# Microcontroller.net
KiCad netlist of a schematic drawn in Altium Designer
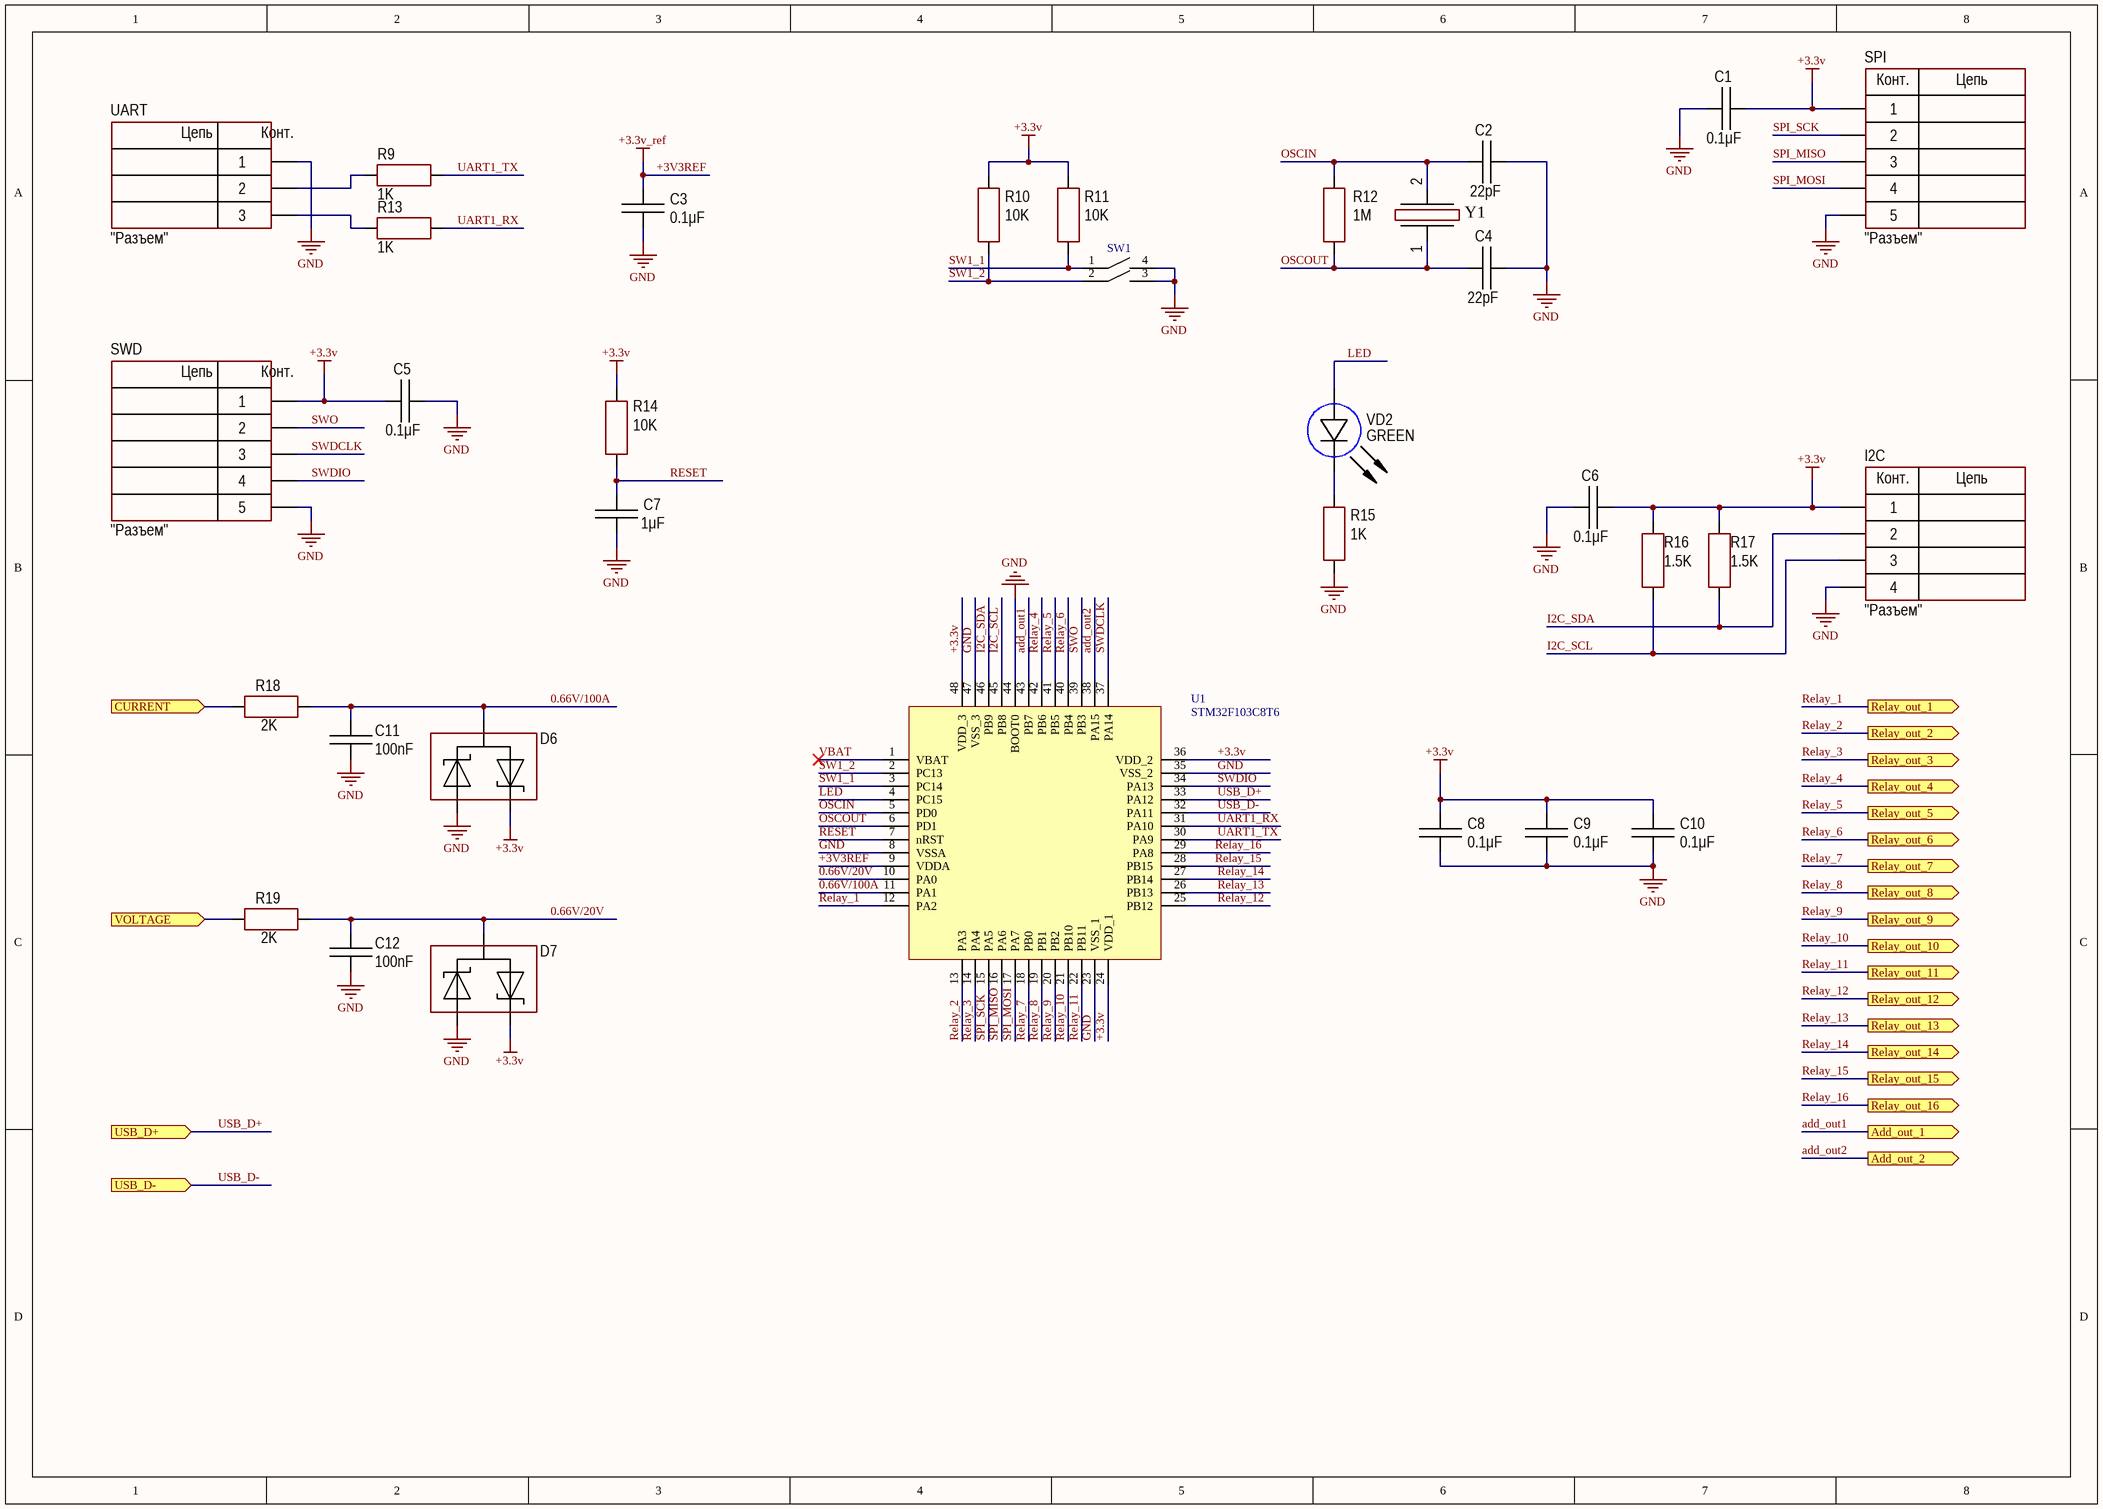
[diagram p0: Microcontroller.SchDoc]

(export (version "E")
  (design (tool "Eeschema 10.0.6"))
  (components
    (comp (ref "C1")
      (value "0.1μF")
      (footprint "StandardCase:CAP: 1206")
      (fields
        (field (name "MANUFACTURER") "Yageo")
        (field (name "PARTNUMBER") "CC1206KRX7R9BB104")
        (field (name "VALUEMANUFACTURERPARTNUMBER") "Ceramic capacitor, 0.1μF, X7R, ±10%, 50V, 1206, -55...+125°C")
      )
      (libsource (lib "Capacitor") (part "Ceramic_1206"))
    )
    (comp (ref "C2")
      (value "22pF")
      (footprint "StandardCase:CAP: 1206")
      (fields
        (field (name "MANUFACTURER") "Yageo")
        (field (name "PARTNUMBER") "CC1206KRX7R9BB104")
        (field (name "VALUEMANUFACTURERPARTNUMBER") "Ceramic capacitor, 22pF, X7R, ±10%, 50V, 1206, -55...+125°C")
      )
      (libsource (lib "Capacitor") (part "Ceramic_1206"))
    )
    (comp (ref "C3")
      (value "0.1μF")
      (footprint "StandardCase:CAP: 1206")
      (fields
        (field (name "MANUFACTURER") "Yageo")
        (field (name "PARTNUMBER") "CC1206KRX7R9BB104")
        (field (name "VALUEMANUFACTURERPARTNUMBER") "Ceramic capacitor, 0.1μF, X7R, ±10%, 50V, 1206, -55...+125°C")
      )
      (libsource (lib "Capacitor") (part "Ceramic_1206"))
    )
    (comp (ref "C4")
      (value "22pF")
      (footprint "StandardCase:CAP: 1206")
      (fields
        (field (name "MANUFACTURER") "Yageo")
        (field (name "PARTNUMBER") "CC1206KRX7R9BB104")
        (field (name "VALUEMANUFACTURERPARTNUMBER") "Ceramic capacitor, 22pF, X7R, ±10%, 50V, 1206, -55...+125°C")
      )
      (libsource (lib "Capacitor") (part "Ceramic_1206"))
    )
    (comp (ref "C5")
      (value "0.1μF")
      (footprint "StandardCase:CAP: 1206")
      (fields
        (field (name "MANUFACTURER") "Yageo")
        (field (name "PARTNUMBER") "CC1206KRX7R9BB104")
        (field (name "VALUEMANUFACTURERPARTNUMBER") "Ceramic capacitor, 0.1μF, X7R, ±10%, 50V, 1206, -55...+125°C")
      )
      (libsource (lib "Capacitor") (part "Ceramic_1206"))
    )
    (comp (ref "C6")
      (value "0.1μF")
      (footprint "StandardCase:CAP: 1206")
      (fields
        (field (name "MANUFACTURER") "Yageo")
        (field (name "PARTNUMBER") "CC1206KRX7R9BB104")
        (field (name "VALUEMANUFACTURERPARTNUMBER") "Ceramic capacitor, 0.1μF, X7R, ±10%, 50V, 1206, -55...+125°C")
      )
      (libsource (lib "Capacitor") (part "Ceramic_1206"))
    )
    (comp (ref "C7")
      (value "1μF")
      (footprint "StandardCase:CAP: 1206")
      (fields
        (field (name "MANUFACTURER") "Yageo")
        (field (name "PARTNUMBER") "CC1206KRX7R9BB104")
        (field (name "VALUEMANUFACTURERPARTNUMBER") "Ceramic capacitor, 1μF, X7R, ±10%, 50V, 1206, -55...+125°C")
      )
      (libsource (lib "Capacitor") (part "Ceramic_1206"))
    )
    (comp (ref "C8")
      (value "0.1μF")
      (footprint "StandardCase:CAP: 1206")
      (fields
        (field (name "MANUFACTURER") "Yageo")
        (field (name "PARTNUMBER") "CC1206KRX7R9BB104")
        (field (name "VALUEMANUFACTURERPARTNUMBER") "Ceramic capacitor, 0.1μF, X7R, ±10%, 50V, 1206, -55...+125°C")
      )
      (libsource (lib "Capacitor") (part "Ceramic_1206"))
    )
    (comp (ref "C9")
      (value "0.1μF")
      (footprint "StandardCase:CAP: 1206")
      (fields
        (field (name "MANUFACTURER") "Yageo")
        (field (name "PARTNUMBER") "CC1206KRX7R9BB104")
        (field (name "VALUEMANUFACTURERPARTNUMBER") "Ceramic capacitor, 0.1μF, X7R, ±10%, 50V, 1206, -55...+125°C")
      )
      (libsource (lib "Capacitor") (part "Ceramic_1206"))
    )
    (comp (ref "C10")
      (value "0.1μF")
      (footprint "StandardCase:CAP: 1206")
      (fields
        (field (name "MANUFACTURER") "Yageo")
        (field (name "PARTNUMBER") "CC1206KRX7R9BB104")
        (field (name "VALUEMANUFACTURERPARTNUMBER") "Ceramic capacitor, 0.1μF, X7R, ±10%, 50V, 1206, -55...+125°C")
      )
      (libsource (lib "Capacitor") (part "Ceramic_1206"))
    )
    (comp (ref "C11")
      (value "100nF")
      (footprint "StandardCase:CAP: 1206")
      (fields
        (field (name "MANUFACTURER") "Yageo")
        (field (name "PARTNUMBER") "CC1206KRX7R9BB104")
        (field (name "VALUEMANUFACTURERPARTNUMBER") "Ceramic capacitor, 100nF, X7R, ±10%, 50V, 1206, -55...+125°C")
      )
      (libsource (lib "Capacitor") (part "Ceramic_1206"))
    )
    (comp (ref "C12")
      (value "100nF")
      (footprint "StandardCase:CAP: 1206")
      (fields
        (field (name "MANUFACTURER") "Yageo")
        (field (name "PARTNUMBER") "CC1206KRX7R9BB104")
        (field (name "VALUEMANUFACTURERPARTNUMBER") "Ceramic capacitor, 100nF, X7R, ±10%, 50V, 1206, -55...+125°C")
      )
      (libsource (lib "Capacitor") (part "Ceramic_1206"))
    )
    (comp (ref "D6")
      (value "~")
      (footprint "StandardCase:SOT23")
      (fields
        (field (name "MANUFACTURER") "Diodes Incorporated")
        (field (name "VALUEMANUFACTURERPARTNUMBER") "BAS40-04, SOT23-3")
        (field (name "VOLTAGE") "40V")
      )
      (libsource (lib "Diode") (part "Schottky_array"))
    )
    (comp (ref "D7")
      (value "~")
      (footprint "StandardCase:SOT23")
      (fields
        (field (name "MANUFACTURER") "Diodes Incorporated")
        (field (name "VALUEMANUFACTURERPARTNUMBER") "BAS40-04, SOT23-3")
        (field (name "VOLTAGE") "40V")
      )
      (libsource (lib "Diode") (part "Schottky_array"))
    )
    (comp (ref "I2C")
      (value "~")
      (footprint "CustomCase:CON: PLS-4")
      (fields
        (field (name "MANUFACTURER") "Connfly")
        (field (name "VALUEMANUFACTURERPARTNUMBER") "Connector, 4pin, 2.54mm, 500VAC, 3A")
        (field (name "PARTNUMBER") "PLS-4")
        (field (name "COMMENTTEXT") "\"Разъем\"")
      )
      (libsource (lib "Connector") (part "PLS-4"))
    )
    (comp (ref "R9")
      (value "1K")
      (footprint "StandardCase:RES: 1206")
      (fields
        (field (name "MANUFACTURER") "Yageo")
        (field (name "PARTNUMBER") "RC1206JR-07100RL")
        (field (name "VALUEMANUFACTURERPARTNUMBER") "Resistor film, 1K, ±5%, 1206, 0.25W, -55...+125°C")
      )
      (libsource (lib "") (part "Resistor_1206_2"))
    )
    (comp (ref "R10")
      (value "10K")
      (footprint "StandardCase:RES: 1206")
      (fields
        (field (name "MANUFACTURER") "Yageo")
        (field (name "PARTNUMBER") "RC1206JR-07100RL")
        (field (name "VALUEMANUFACTURERPARTNUMBER") "Resistor, 10K, 1206")
      )
      (libsource (lib "Resistor") (part "Resistor_1206"))
    )
    (comp (ref "R11")
      (value "10K")
      (footprint "StandardCase:RES: 1206")
      (fields
        (field (name "MANUFACTURER") "Yageo")
        (field (name "PARTNUMBER") "RC1206JR-07100RL")
        (field (name "VALUEMANUFACTURERPARTNUMBER") "Resistor, 10K, 1206")
      )
      (libsource (lib "Resistor") (part "Resistor_1206"))
    )
    (comp (ref "R12")
      (value "1M")
      (footprint "StandardCase:RES: 1206")
      (fields
        (field (name "MANUFACTURER") "Yageo")
        (field (name "PARTNUMBER") "RC1206JR-07100RL")
        (field (name "VALUEMANUFACTURERPARTNUMBER") "Resistor film, 1M, ±5%, 1206, 0.25W, -55...+125°C")
      )
      (libsource (lib "Resistor") (part "Resistor_1206"))
    )
    (comp (ref "R13")
      (value "1K")
      (footprint "StandardCase:RES: 1206")
      (fields
        (field (name "MANUFACTURER") "Yageo")
        (field (name "PARTNUMBER") "RC1206JR-07100RL")
        (field (name "VALUEMANUFACTURERPARTNUMBER") "Resistor film, 1K, ±5%, 1206, 0.25W, -55...+125°C")
      )
      (libsource (lib "") (part "Resistor_1206_2"))
    )
    (comp (ref "R14")
      (value "10K")
      (footprint "StandardCase:RES: 1206")
      (fields
        (field (name "MANUFACTURER") "Yageo")
        (field (name "PARTNUMBER") "RC1206JR-07100RL")
        (field (name "VALUEMANUFACTURERPARTNUMBER") "Resistor film, 10K, ±5%, 1206, 0.25W, -55...+125°C")
      )
      (libsource (lib "Resistor") (part "Resistor_1206"))
    )
    (comp (ref "R15")
      (value "1K")
      (footprint "StandardCase:RES: 1206")
      (fields
        (field (name "MANUFACTURER") "Yageo")
        (field (name "PARTNUMBER") "RC1206JR-07100RL")
        (field (name "VALUEMANUFACTURERPARTNUMBER") "Resistor film, 1K, ±5%, 1206, 0.25W, -55...+125°C")
      )
      (libsource (lib "Resistor") (part "Resistor_1206"))
    )
    (comp (ref "R16")
      (value "1.5K")
      (footprint "StandardCase:RES: 1206")
      (fields
        (field (name "MANUFACTURER") "Yageo")
        (field (name "PARTNUMBER") "RC1206JR-07100RL")
        (field (name "VALUEMANUFACTURERPARTNUMBER") "Resistor film, 1.5K, ±5%, 1206, 0.25W, -55...+125°C")
      )
      (libsource (lib "") (part "Resistor_1206_1"))
    )
    (comp (ref "R17")
      (value "1.5K")
      (footprint "StandardCase:RES: 1206")
      (fields
        (field (name "MANUFACTURER") "Yageo")
        (field (name "PARTNUMBER") "RC1206JR-07100RL")
        (field (name "VALUEMANUFACTURERPARTNUMBER") "Resistor film, 1.5K, ±5%, 1206, 0.25W, -55...+125°C")
      )
      (libsource (lib "") (part "Resistor_1206_1"))
    )
    (comp (ref "R18")
      (value "2K")
      (footprint "StandardCase:RES: 1206")
      (fields
        (field (name "MANUFACTURER") "Yageo")
        (field (name "PARTNUMBER") "RC1206JR-07100RL")
        (field (name "VALUEMANUFACTURERPARTNUMBER") "Resistor film, 2K, ±5%, 1206, 0.25W, -55...+125°C")
      )
      (libsource (lib "") (part "Resistor_1206_2"))
    )
    (comp (ref "R19")
      (value "2K")
      (footprint "StandardCase:RES: 1206")
      (fields
        (field (name "MANUFACTURER") "Yageo")
        (field (name "PARTNUMBER") "RC1206JR-07100RL")
        (field (name "VALUEMANUFACTURERPARTNUMBER") "Resistor film, 2K, ±5%, 1206, 0.25W, -55...+125°C")
      )
      (libsource (lib "") (part "Resistor_1206_2"))
    )
    (comp (ref "SPI")
      (value "~")
      (footprint "CustomCase:CON: PLS-5")
      (fields
        (field (name "MANUFACTURER") "Connfly")
        (field (name "VALUEMANUFACTURERPARTNUMBER") "Connector, 5pin, 2.54mm, 500VAC, 3A")
        (field (name "PARTNUMBER") "PLS-5")
        (field (name "COMMENTTEXT") "\"Разъем\"")
      )
      (libsource (lib "Connector") (part "PLS-5"))
    )
    (comp (ref "SW1")
      (value "~")
      (footprint "PcbLib1:DPL-2")
      (fields
        (field (name "PARTNUMBER") "NDP-02")
        (field (name "VALUEMANUFACTURERPARTNUMBER") "NDP-02, DPL-02")
      )
      (libsource (lib "Schlib1") (part "NDP-02"))
    )
    (comp (ref "SWD")
      (value "~")
      (footprint "CustomCase:CON: PLS-5")
      (fields
        (field (name "MANUFACTURER") "Connfly")
        (field (name "VALUEMANUFACTURERPARTNUMBER") "Connector, 5pin, 2.54mm, 500VAC, 3A")
        (field (name "PARTNUMBER") "PLS-5")
        (field (name "COMMENTTEXT") "\"Разъем\"")
      )
      (libsource (lib "") (part "PLS-5_1"))
    )
    (comp (ref "U1")
      (value "STM32F103C8T6")
      (footprint "StandardCase:48-LQFP")
      (libsource (lib "Schlib1") (part "STM32F103C8T6"))
    )
    (comp (ref "UART")
      (value "~")
      (footprint "CustomCase:CON: PLS-3")
      (fields
        (field (name "MANUFACTURER") "Connfly")
        (field (name "VALUEMANUFACTURERPARTNUMBER") "Connector, 3pin, 2.54mm, 500VAC, 3A")
        (field (name "PARTNUMBER") "PLS-3")
        (field (name "COMMENTTEXT") "\"Разъем\"")
      )
      (libsource (lib "Connector") (part "PLS-3"))
    )
    (comp (ref "VD2")
      (value "~")
      (footprint "StandardCase:LED: 1206G")
      (fields
        (field (name "VALUEMANUFACTURERPARTNUMBER") "LED, Green, *, *, *, -55...+150°C")
        (field (name "COLOR") "GREEN")
      )
      (libsource (lib "Diode") (part "LED_single"))
    )
    (comp (ref "Y1")
      (value "~")
      (footprint "PcbLib1:HC49SM")
      (fields
        (field (name "PARTNUMBER") "HC49SM-16.000MHZ-20PF")
        (field (name "VALUEMANUFACTURERPARTNUMBER") "HC49SM-16.000MHZ-20PF, HC49SM")
      )
      (libsource (lib "Schlib1") (part "HC49SM"))
    )
  )
  (nets
    (net (code "1") (name "+3.3v") (class "Default")
      (node (ref "C1") (pin "2") (pinfunction "2_2") (pintype "power_in"))
      (node (ref "C10") (pin "2") (pinfunction "2_2") (pintype "power_in"))
      (node (ref "C5") (pin "1") (pinfunction "1_1") (pintype "power_in"))
      (node (ref "C6") (pin "2") (pinfunction "2_2") (pintype "power_in"))
      (node (ref "C8") (pin "2") (pinfunction "2_2") (pintype "power_in"))
      (node (ref "C9") (pin "2") (pinfunction "2_2") (pintype "power_in"))
      (node (ref "D6") (pin "2") (pinfunction "2_2") (pintype "passive"))
      (node (ref "D7") (pin "2") (pinfunction "2_2") (pintype "passive"))
      (node (ref "I2C") (pin "1") (pinfunction "1_1") (pintype "passive"))
      (node (ref "R10") (pin "2") (pinfunction "2_2") (pintype "passive"))
      (node (ref "R11") (pin "2") (pinfunction "2_2") (pintype "passive"))
      (node (ref "R14") (pin "2") (pinfunction "2_2") (pintype "passive"))
      (node (ref "R16") (pin "1") (pinfunction "1_1") (pintype "passive"))
      (node (ref "R17") (pin "1") (pinfunction "1_1") (pintype "passive"))
      (node (ref "SPI") (pin "1") (pinfunction "1_1") (pintype "passive"))
      (node (ref "SWD") (pin "1") (pinfunction "1_1") (pintype "passive"))
      (node (ref "U1") (pin "24") (pinfunction "VDD_1_24") (pintype "passive"))
      (node (ref "U1") (pin "36") (pinfunction "VDD_2_36") (pintype "passive"))
      (node (ref "U1") (pin "48") (pinfunction "VDD_3_48") (pintype "passive"))
    )
    (net (code "2") (name "+3.3v_ref") (class "Default")
      (node (ref "C3") (pin "2") (pinfunction "2_2") (pintype "power_in"))
      (node (ref "U1") (pin "9") (pinfunction "VDDA_9") (pintype "passive"))
    )
    (net (code "3") (name "/0.66V{slash}20V") (class "Default")
      (node (ref "C12") (pin "2") (pinfunction "2_2") (pintype "power_in"))
      (node (ref "D7") (pin "3") (pinfunction "3_3") (pintype "passive"))
      (node (ref "R19") (pin "1") (pinfunction "1_1") (pintype "passive"))
      (node (ref "U1") (pin "10") (pinfunction "PA0_10") (pintype "passive"))
    )
    (net (code "4") (name "/0.66V{slash}100A") (class "Default")
      (node (ref "C11") (pin "2") (pinfunction "2_2") (pintype "power_in"))
      (node (ref "D6") (pin "3") (pinfunction "3_3") (pintype "passive"))
      (node (ref "R18") (pin "1") (pinfunction "1_1") (pintype "passive"))
      (node (ref "U1") (pin "11") (pinfunction "PA1_11") (pintype "passive"))
    )
    (net (code "5") (name "/CURRENT") (class "Default")
      (node (ref "R18") (pin "2") (pinfunction "2_2") (pintype "passive"))
    )
    (net (code "6") (name "/I2C_SCL") (class "Default")
      (node (ref "I2C") (pin "3") (pinfunction "3_3") (pintype "power_in"))
      (node (ref "R16") (pin "2") (pinfunction "2_2") (pintype "passive"))
      (node (ref "U1") (pin "45") (pinfunction "PB8_45") (pintype "passive"))
    )
    (net (code "7") (name "/I2C_SDA") (class "Default")
      (node (ref "I2C") (pin "2") (pinfunction "2_2") (pintype "passive"))
      (node (ref "R17") (pin "2") (pinfunction "2_2") (pintype "passive"))
      (node (ref "U1") (pin "46") (pinfunction "PB9_46") (pintype "passive"))
    )
    (net (code "8") (name "/LED") (class "Default")
      (node (ref "U1") (pin "4") (pinfunction "PC15_4") (pintype "passive"))
      (node (ref "VD2") (pin "1") (pinfunction "A_1") (pintype "passive"))
    )
    (net (code "9") (name "/OSCIN") (class "Default")
      (node (ref "C2") (pin "2") (pinfunction "2_2") (pintype "power_in"))
      (node (ref "R12") (pin "2") (pinfunction "2_2") (pintype "passive"))
      (node (ref "U1") (pin "5") (pinfunction "PD0_5") (pintype "passive"))
      (node (ref "Y1") (pin "2") (pinfunction "2_2") (pintype "passive"))
    )
    (net (code "10") (name "/OSCOUT") (class "Default")
      (node (ref "C4") (pin "2") (pinfunction "2_2") (pintype "power_in"))
      (node (ref "R12") (pin "1") (pinfunction "1_1") (pintype "passive"))
      (node (ref "U1") (pin "6") (pinfunction "PD1_6") (pintype "passive"))
      (node (ref "Y1") (pin "1") (pinfunction "1_1") (pintype "passive"))
    )
    (net (code "11") (name "/RESET") (class "Default")
      (node (ref "C7") (pin "2") (pinfunction "2_2") (pintype "power_in"))
      (node (ref "R14") (pin "1") (pinfunction "1_1") (pintype "passive"))
      (node (ref "U1") (pin "7") (pinfunction "nRST_7") (pintype "passive"))
    )
    (net (code "12") (name "/Relay_1") (class "Default")
      (node (ref "U1") (pin "12") (pinfunction "PA2_12") (pintype "passive"))
    )
    (net (code "13") (name "/Relay_2") (class "Default")
      (node (ref "U1") (pin "13") (pinfunction "PA3_13") (pintype "passive"))
    )
    (net (code "14") (name "/Relay_3") (class "Default")
      (node (ref "U1") (pin "14") (pinfunction "PA4_14") (pintype "passive"))
    )
    (net (code "15") (name "/Relay_4") (class "Default")
      (node (ref "U1") (pin "42") (pinfunction "PB6_42") (pintype "passive"))
    )
    (net (code "16") (name "/Relay_5") (class "Default")
      (node (ref "U1") (pin "41") (pinfunction "PB5_41") (pintype "passive"))
    )
    (net (code "17") (name "/Relay_6") (class "Default")
      (node (ref "U1") (pin "40") (pinfunction "PB4_40") (pintype "passive"))
    )
    (net (code "18") (name "/Relay_7") (class "Default")
      (node (ref "U1") (pin "18") (pinfunction "PB0_18") (pintype "passive"))
    )
    (net (code "19") (name "/Relay_8") (class "Default")
      (node (ref "U1") (pin "19") (pinfunction "PB1_19") (pintype "passive"))
    )
    (net (code "20") (name "/Relay_9") (class "Default")
      (node (ref "U1") (pin "20") (pinfunction "PB2_20") (pintype "passive"))
    )
    (net (code "21") (name "/Relay_10") (class "Default")
      (node (ref "U1") (pin "21") (pinfunction "PB10_21") (pintype "passive"))
    )
    (net (code "22") (name "/Relay_11") (class "Default")
      (node (ref "U1") (pin "22") (pinfunction "PB11_22") (pintype "passive"))
    )
    (net (code "23") (name "/Relay_12") (class "Default")
      (node (ref "U1") (pin "25") (pinfunction "PB12_25") (pintype "passive"))
    )
    (net (code "24") (name "/Relay_13") (class "Default")
      (node (ref "U1") (pin "26") (pinfunction "PB13_26") (pintype "passive"))
    )
    (net (code "25") (name "/Relay_14") (class "Default")
      (node (ref "U1") (pin "27") (pinfunction "PB14_27") (pintype "passive"))
    )
    (net (code "26") (name "/Relay_15") (class "Default")
      (node (ref "U1") (pin "28") (pinfunction "PB15_28") (pintype "passive"))
    )
    (net (code "27") (name "/Relay_16") (class "Default")
      (node (ref "U1") (pin "29") (pinfunction "PA8_29") (pintype "passive"))
    )
    (net (code "28") (name "/SPI_MISO") (class "Default")
      (node (ref "SPI") (pin "3") (pinfunction "3_3") (pintype "power_in"))
      (node (ref "U1") (pin "16") (pinfunction "PA6_16") (pintype "passive"))
    )
    (net (code "29") (name "/SPI_MOSI") (class "Default")
      (node (ref "SPI") (pin "4") (pinfunction "4_4") (pintype "power_in"))
      (node (ref "U1") (pin "17") (pinfunction "PA7_17") (pintype "passive"))
    )
    (net (code "30") (name "/SPI_SCK") (class "Default")
      (node (ref "SPI") (pin "2") (pinfunction "2_2") (pintype "passive"))
      (node (ref "U1") (pin "15") (pinfunction "PA5_15") (pintype "passive"))
    )
    (net (code "31") (name "/SW1_1") (class "Default")
      (node (ref "R11") (pin "1") (pinfunction "1_1") (pintype "passive"))
      (node (ref "SW1") (pin "1") (pinfunction "1_1") (pintype "passive"))
      (node (ref "U1") (pin "3") (pinfunction "PC14_3") (pintype "passive"))
    )
    (net (code "32") (name "/SW1_2") (class "Default")
      (node (ref "R10") (pin "1") (pinfunction "1_1") (pintype "passive"))
      (node (ref "SW1") (pin "2") (pinfunction "2_2") (pintype "passive"))
      (node (ref "U1") (pin "2") (pinfunction "PC13_2") (pintype "passive"))
    )
    (net (code "33") (name "/SWDCLK") (class "Default")
      (node (ref "SWD") (pin "3") (pinfunction "3_3") (pintype "power_in"))
      (node (ref "U1") (pin "37") (pinfunction "PA14_37") (pintype "passive"))
    )
    (net (code "34") (name "/SWDIO") (class "Default")
      (node (ref "SWD") (pin "4") (pinfunction "4_4") (pintype "power_in"))
      (node (ref "U1") (pin "34") (pinfunction "PA13_34") (pintype "passive"))
    )
    (net (code "35") (name "/SWO") (class "Default")
      (node (ref "SWD") (pin "2") (pinfunction "2_2") (pintype "passive"))
      (node (ref "U1") (pin "39") (pinfunction "PB3_39") (pintype "passive"))
    )
    (net (code "36") (name "/UART1_RX") (class "Default")
      (node (ref "R13") (pin "1") (pinfunction "1_1") (pintype "passive"))
      (node (ref "U1") (pin "31") (pinfunction "PA10_31") (pintype "passive"))
    )
    (net (code "37") (name "/UART1_TX") (class "Default")
      (node (ref "R9") (pin "1") (pinfunction "1_1") (pintype "passive"))
      (node (ref "U1") (pin "30") (pinfunction "PA9_30") (pintype "passive"))
    )
    (net (code "38") (name "/USB_D+") (class "Default")
      (node (ref "U1") (pin "33") (pinfunction "PA12_33") (pintype "passive"))
    )
    (net (code "39") (name "/USB_D-") (class "Default")
      (node (ref "U1") (pin "32") (pinfunction "PA11_32") (pintype "passive"))
    )
    (net (code "40") (name "/VBAT") (class "Default")
      (node (ref "U1") (pin "1") (pinfunction "VBAT_1") (pintype "passive+no_connect"))
    )
    (net (code "41") (name "/VOLTAGE") (class "Default")
      (node (ref "R19") (pin "2") (pinfunction "2_2") (pintype "passive"))
    )
    (net (code "42") (name "/add_out1") (class "Default")
      (node (ref "U1") (pin "43") (pinfunction "PB7_43") (pintype "passive"))
    )
    (net (code "43") (name "/add_out2") (class "Default")
      (node (ref "U1") (pin "38") (pinfunction "PA15_38") (pintype "passive"))
    )
    (net (code "44") (name "GND") (class "Default")
      (node (ref "C1") (pin "1") (pinfunction "1_1") (pintype "power_in"))
      (node (ref "C10") (pin "1") (pinfunction "1_1") (pintype "power_in"))
      (node (ref "C11") (pin "1") (pinfunction "1_1") (pintype "power_in"))
      (node (ref "C12") (pin "1") (pinfunction "1_1") (pintype "power_in"))
      (node (ref "C2") (pin "1") (pinfunction "1_1") (pintype "power_in"))
      (node (ref "C3") (pin "1") (pinfunction "1_1") (pintype "power_in"))
      (node (ref "C4") (pin "1") (pinfunction "1_1") (pintype "power_in"))
      (node (ref "C5") (pin "2") (pinfunction "2_2") (pintype "power_in"))
      (node (ref "C6") (pin "1") (pinfunction "1_1") (pintype "power_in"))
      (node (ref "C7") (pin "1") (pinfunction "1_1") (pintype "power_in"))
      (node (ref "C8") (pin "1") (pinfunction "1_1") (pintype "power_in"))
      (node (ref "C9") (pin "1") (pinfunction "1_1") (pintype "power_in"))
      (node (ref "D6") (pin "1") (pinfunction "1_1") (pintype "passive"))
      (node (ref "D7") (pin "1") (pinfunction "1_1") (pintype "passive"))
      (node (ref "I2C") (pin "4") (pinfunction "4_4") (pintype "power_in"))
      (node (ref "R15") (pin "1") (pinfunction "1_1") (pintype "passive"))
      (node (ref "SPI") (pin "5") (pinfunction "5_5") (pintype "power_in"))
      (node (ref "SW1") (pin "3") (pinfunction "3_3") (pintype "passive"))
      (node (ref "SW1") (pin "4") (pinfunction "4_4") (pintype "passive"))
      (node (ref "SWD") (pin "5") (pinfunction "5_5") (pintype "power_in"))
      (node (ref "U1") (pin "23") (pinfunction "VSS_1_23") (pintype "passive"))
      (node (ref "U1") (pin "35") (pinfunction "VSS_2_35") (pintype "passive"))
      (node (ref "U1") (pin "44") (pinfunction "BOOT0_44") (pintype "passive"))
      (node (ref "U1") (pin "47") (pinfunction "VSS_3_47") (pintype "passive"))
      (node (ref "U1") (pin "8") (pinfunction "VSSA_8") (pintype "passive"))
      (node (ref "UART") (pin "1") (pinfunction "1_1") (pintype "passive"))
    )
    (net (code "45") (name "Net-(R9-Pad2)") (class "Default")
      (node (ref "R9") (pin "2") (pinfunction "2_2") (pintype "passive"))
      (node (ref "UART") (pin "2") (pinfunction "2_2") (pintype "passive"))
    )
    (net (code "46") (name "Net-(R13-Pad2)") (class "Default")
      (node (ref "R13") (pin "2") (pinfunction "2_2") (pintype "passive"))
      (node (ref "UART") (pin "3") (pinfunction "3_3") (pintype "power_in"))
    )
    (net (code "47") (name "Net-(VD2-C)") (class "Default")
      (node (ref "R15") (pin "2") (pinfunction "2_2") (pintype "passive"))
      (node (ref "VD2") (pin "2") (pinfunction "C_2") (pintype "passive"))
    )
  )
)
